# Motor_Top_module.net
KiCad netlist of a schematic drawn in Altium Designer
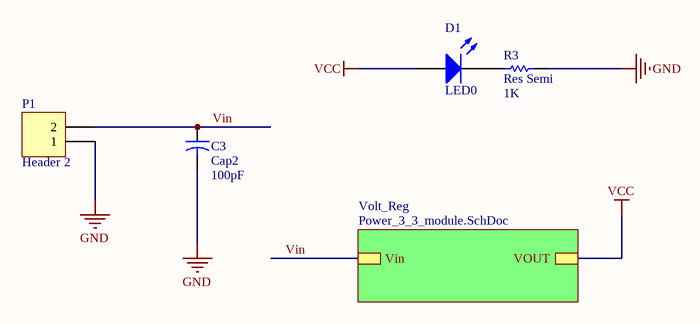
[diagram p0: Motor_Top_module.SchDoc]

(export (version "E")
  (design (tool "Eeschema 10.0.6"))
  (components
    (comp (ref "C3")
      (value "Cap2")
      (footprint "CAPR5-4X5")
      (description "Capacitor")
      (fields (field (name "ALTIUM_VALUE") "100pF") (field (name "PUBLISHER") "Altium Limited"))
      (libsource (lib "Miscellaneous Devices") (part "Cap2"))
    )
    (comp (ref "D1")
      (value "LED0")
      (footprint "LED-0")
      (description "Typical INFRARED GaAs LED")
      (fields (field (name "PUBLISHER") "Altium Limited"))
      (libsource (lib "Miscellaneous Devices") (part "LED0"))
    )
    (comp (ref "P1")
      (value "Header 2")
      (footprint "HDR1X2")
      (description "Header, 2-Pin")
      (fields (field (name "PUBLISHER") "Altium Limited"))
      (libsource (lib "Miscellaneous Connectors") (part "Header 2"))
    )
    (comp (ref "R3")
      (value "Res Semi")
      (footprint "AXIAL-0.5")
      (description "Semiconductor Resistor")
      (fields (field (name "ALTIUM_VALUE") "1K") (field (name "PUBLISHER") "Altium Limited"))
      (libsource (lib "Miscellaneous Devices") (part "Res Semi"))
    )
  )
  (nets
    (net (code "1") (name "/Vin") (class "Default")
      (node (ref "C3") (pin "1") (pinfunction "1_1") (pintype "passive"))
      (node (ref "P1") (pin "2") (pinfunction "2_2") (pintype "passive"))
    )
    (net (code "2") (name "GND") (class "Default")
      (node (ref "C3") (pin "2") (pinfunction "2_2") (pintype "passive"))
      (node (ref "P1") (pin "1") (pinfunction "1_1") (pintype "passive"))
      (node (ref "R3") (pin "2") (pinfunction "2_2") (pintype "passive"))
    )
    (net (code "3") (name "Net-(D1-K)") (class "Default")
      (node (ref "D1") (pin "2") (pinfunction "K_2") (pintype "passive"))
      (node (ref "R3") (pin "1") (pinfunction "1_1") (pintype "passive"))
    )
    (net (code "4") (name "VCC") (class "Default")
      (node (ref "D1") (pin "1") (pinfunction "A_1") (pintype "passive"))
    )
  )
)
